# I2C.net
KiCad netlist of a schematic drawn in Altium Designer
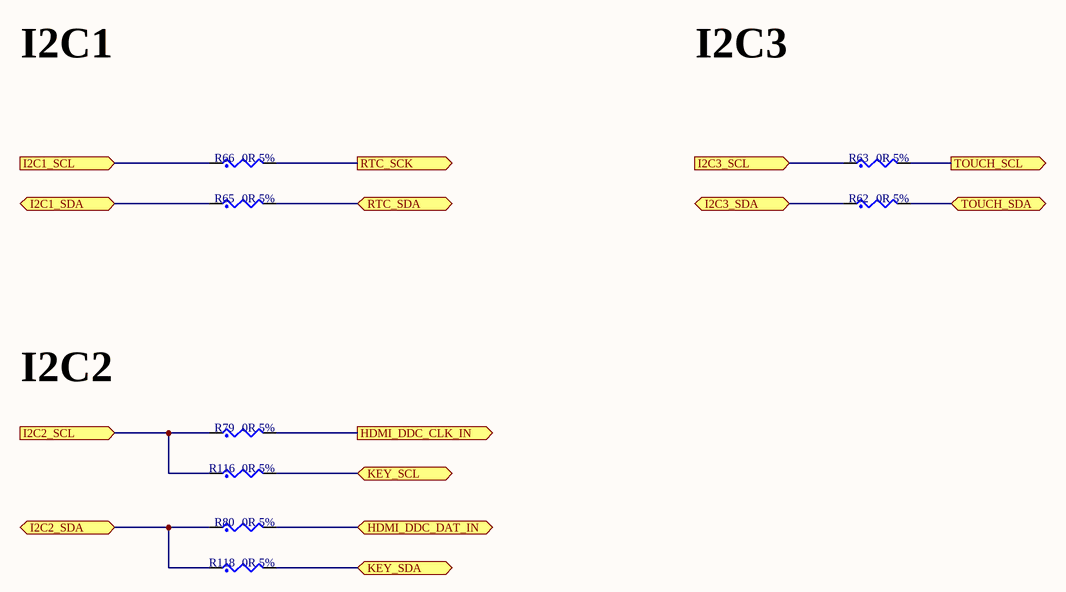
[diagram p0: I2C.SchDoc]

(export (version "E")
  (design (tool "Eeschema 10.0.6"))
  (components
    (comp (ref "R62")
      (value "0R 5%")
      (footprint "SR0603")
      (libsource (lib "MY-I.MX6-SCH_Library") (part "RES"))
    )
    (comp (ref "R63")
      (value "0R 5%")
      (footprint "SR0603")
      (libsource (lib "MY-I.MX6-SCH_Library") (part "RES"))
    )
    (comp (ref "R65")
      (value "0R 5%")
      (footprint "SR0603")
      (libsource (lib "MY-I.MX6-SCH_Library") (part "RES"))
    )
    (comp (ref "R66")
      (value "0R 5%")
      (footprint "SR0603")
      (libsource (lib "MY-I.MX6-SCH_Library") (part "RES"))
    )
    (comp (ref "R79")
      (value "0R 5%")
      (footprint "SR0603")
      (libsource (lib "MY-I.MX6-SCH_Library") (part "RES"))
    )
    (comp (ref "R80")
      (value "0R 5%")
      (footprint "SR0603")
      (libsource (lib "MY-I.MX6-SCH_Library") (part "RES"))
    )
    (comp (ref "R116")
      (value "0R 5%")
      (footprint "SR0603")
      (libsource (lib "MY-I.MX6-SCH_Library") (part "RES"))
    )
    (comp (ref "R118")
      (value "0R 5%")
      (footprint "SR0603")
      (libsource (lib "MY-I.MX6-SCH_Library") (part "RES"))
    )
  )
  (nets
    (net (code "1") (name "/HDMI_DDC_CLK_IN") (class "Default")
      (node (ref "R79") (pin "2") (pinfunction "2_2") (pintype "passive"))
    )
    (net (code "2") (name "/HDMI_DDC_DAT_IN") (class "Default")
      (node (ref "R80") (pin "2") (pinfunction "2_2") (pintype "passive"))
    )
    (net (code "3") (name "/I2C1_SCL") (class "Default")
      (node (ref "R66") (pin "1") (pinfunction "1_1") (pintype "passive"))
    )
    (net (code "4") (name "/I2C1_SDA") (class "Default")
      (node (ref "R65") (pin "1") (pinfunction "1_1") (pintype "passive"))
    )
    (net (code "5") (name "/I2C2_SCL") (class "Default")
      (node (ref "R116") (pin "1") (pinfunction "1_1") (pintype "passive"))
      (node (ref "R79") (pin "1") (pinfunction "1_1") (pintype "passive"))
    )
    (net (code "6") (name "/I2C2_SDA") (class "Default")
      (node (ref "R118") (pin "1") (pinfunction "1_1") (pintype "passive"))
      (node (ref "R80") (pin "1") (pinfunction "1_1") (pintype "passive"))
    )
    (net (code "7") (name "/I2C3_SCL") (class "Default")
      (node (ref "R63") (pin "1") (pinfunction "1_1") (pintype "passive"))
    )
    (net (code "8") (name "/I2C3_SDA") (class "Default")
      (node (ref "R62") (pin "1") (pinfunction "1_1") (pintype "passive"))
    )
    (net (code "9") (name "/KEY_SCL") (class "Default")
      (node (ref "R116") (pin "2") (pinfunction "2_2") (pintype "passive"))
    )
    (net (code "10") (name "/KEY_SDA") (class "Default")
      (node (ref "R118") (pin "2") (pinfunction "2_2") (pintype "passive"))
    )
    (net (code "11") (name "/RTC_SCK") (class "Default")
      (node (ref "R66") (pin "2") (pinfunction "2_2") (pintype "passive"))
    )
    (net (code "12") (name "/RTC_SDA") (class "Default")
      (node (ref "R65") (pin "2") (pinfunction "2_2") (pintype "passive"))
    )
    (net (code "13") (name "/TOUCH_SCL") (class "Default")
      (node (ref "R63") (pin "2") (pinfunction "2_2") (pintype "passive"))
    )
    (net (code "14") (name "/TOUCH_SDA") (class "Default")
      (node (ref "R62") (pin "2") (pinfunction "2_2") (pintype "passive"))
    )
  )
)
